# laser_scanner.net
KiCad netlist of a schematic drawn in EAGLE
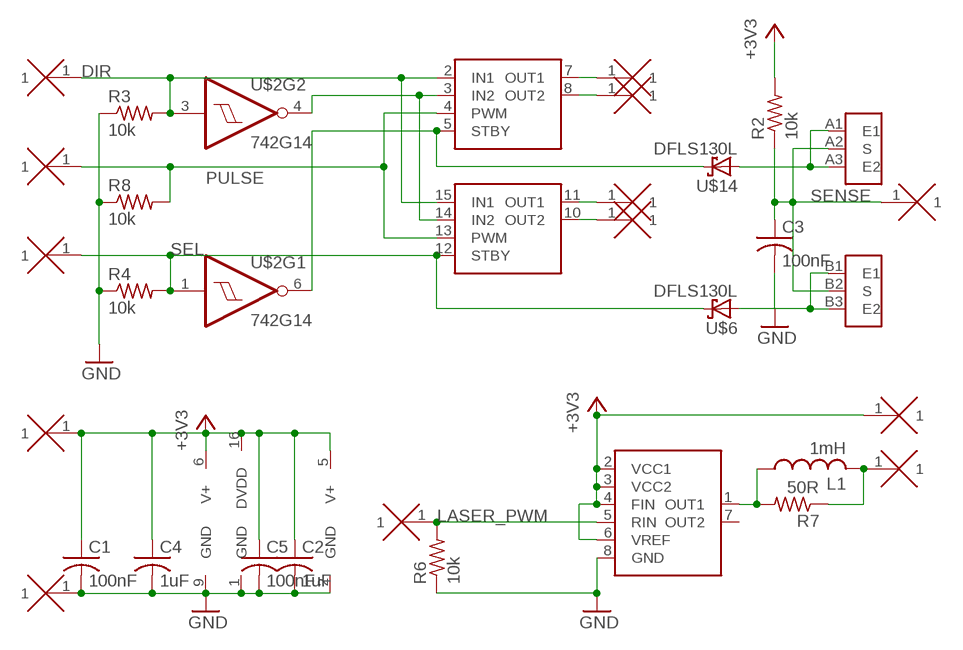
[diagram p0: schematic, sheet 1]

(export (version "E")
  (design (tool "Eeschema 10.0.6"))
  (components
    (comp (ref "C1")
      (value "100nF")
      (footprint "eagle-import:C0603")
      (libsource (lib "eagle-import") (part "C-USC0603"))
    )
    (comp (ref "C2")
      (value "1uF")
      (footprint "eagle-import:C0603")
      (libsource (lib "eagle-import") (part "C-USC0603"))
    )
    (comp (ref "C3")
      (value "100nF")
      (footprint "eagle-import:C0603")
      (libsource (lib "eagle-import") (part "C-USC0603"))
    )
    (comp (ref "C4")
      (value "1uF")
      (footprint "eagle-import:C0603")
      (libsource (lib "eagle-import") (part "C-USC0603"))
    )
    (comp (ref "C5")
      (value "100nF")
      (footprint "eagle-import:C0603")
      (libsource (lib "eagle-import") (part "C-USC0603"))
    )
    (comp (ref "GALVO_DIR")
      (value "PAD-0.6_1.8")
      (footprint "eagle-import:PAD_0.6_1.8")
      (libsource (lib "eagle-import") (part "PAD-0.6_1.8"))
    )
    (comp (ref "GALVO_PULSE")
      (value "PAD-0.6_1.8")
      (footprint "eagle-import:PAD_0.6_1.8")
      (libsource (lib "eagle-import") (part "PAD-0.6_1.8"))
    )
    (comp (ref "GALVO_SEL")
      (value "PAD-0.6_1.8")
      (footprint "eagle-import:PAD_0.6_1.8")
      (libsource (lib "eagle-import") (part "PAD-0.6_1.8"))
    )
    (comp (ref "GALVO_SENSE")
      (value "PAD-0.6_1.8")
      (footprint "eagle-import:PAD_0.6_1.8")
      (libsource (lib "eagle-import") (part "PAD-0.6_1.8"))
    )
    (comp (ref "GND")
      (value "PAD-0.6_1.8")
      (footprint "eagle-import:PAD_0.6_1.8")
      (libsource (lib "eagle-import") (part "PAD-0.6_1.8"))
    )
    (comp (ref "L+")
      (value "PAD-0.6_1.8")
      (footprint "eagle-import:PAD_0.6_1.8")
      (libsource (lib "eagle-import") (part "PAD-0.6_1.8"))
    )
    (comp (ref "L-")
      (value "PAD-0.6_1.8")
      (footprint "eagle-import:PAD_0.6_1.8")
      (libsource (lib "eagle-import") (part "PAD-0.6_1.8"))
    )
    (comp (ref "L1")
      (value "1mH")
      (footprint "eagle-import:L7070")
      (libsource (lib "eagle-import") (part "L-US"))
    )
    (comp (ref "LASER_PWM")
      (value "PAD-0.6_1.8")
      (footprint "eagle-import:PAD_0.6_1.8")
      (libsource (lib "eagle-import") (part "PAD-0.6_1.8"))
    )
    (comp (ref "MA1")
      (value "PAD-0.6_1.8")
      (footprint "eagle-import:PAD_0.6_1.8")
      (libsource (lib "eagle-import") (part "PAD-0.6_1.8"))
    )
    (comp (ref "MA2")
      (value "PAD-0.6_1.8")
      (footprint "eagle-import:PAD_0.6_1.8")
      (libsource (lib "eagle-import") (part "PAD-0.6_1.8"))
    )
    (comp (ref "MB1")
      (value "PAD-0.6_1.8")
      (footprint "eagle-import:PAD_0.6_1.8")
      (libsource (lib "eagle-import") (part "PAD-0.6_1.8"))
    )
    (comp (ref "MB2")
      (value "PAD-0.6_1.8")
      (footprint "eagle-import:PAD_0.6_1.8")
      (libsource (lib "eagle-import") (part "PAD-0.6_1.8"))
    )
    (comp (ref "R2")
      (value "10k")
      (footprint "eagle-import:R0603")
      (libsource (lib "eagle-import") (part "R-US_R0603"))
    )
    (comp (ref "R3")
      (value "10k")
      (footprint "eagle-import:R0603")
      (libsource (lib "eagle-import") (part "R-US_R0603"))
    )
    (comp (ref "R4")
      (value "10k")
      (footprint "eagle-import:R0603")
      (libsource (lib "eagle-import") (part "R-US_R0603"))
    )
    (comp (ref "R6")
      (value "10k")
      (footprint "eagle-import:R0603")
      (libsource (lib "eagle-import") (part "R-US_R0603"))
    )
    (comp (ref "R7")
      (value "50R")
      (footprint "eagle-import:R0603")
      (libsource (lib "eagle-import") (part "R-US_R0603"))
    )
    (comp (ref "R8")
      (value "10k")
      (footprint "eagle-import:R0603")
      (libsource (lib "eagle-import") (part "R-US_R0603"))
    )
    (comp (ref "U$1")
      (value "TB6552")
      (footprint "eagle-import:TSSOP16")
      (libsource (lib "eagle-import") (part "TB6552"))
    )
    (comp (ref "U$2")
      (value "742G14")
      (footprint "eagle-import:SOT23-6")
      (libsource (lib "eagle-import") (part "742G14"))
    )
    (comp (ref "U$3")
      (value "BD6211")
      (footprint "eagle-import:SOP-08")
      (libsource (lib "eagle-import") (part "BD6211"))
    )
    (comp (ref "U$6")
      (value "DFLS130L")
      (footprint "eagle-import:POWERDI323")
      (libsource (lib "eagle-import") (part "DFLS130L"))
    )
    (comp (ref "U$7")
      (value "LASER_SLIDER")
      (footprint "eagle-import:LASER_SCANNER")
      (libsource (lib "eagle-import") (part "LASER_SLIDER"))
    )
    (comp (ref "U$14")
      (value "DFLS130L")
      (footprint "eagle-import:POWERDI323")
      (libsource (lib "eagle-import") (part "DFLS130L"))
    )
    (comp (ref "VCC")
      (value "PAD-0.6_1.8")
      (footprint "eagle-import:PAD_0.6_1.8")
      (libsource (lib "eagle-import") (part "PAD-0.6_1.8"))
    )
  )
  (nets
    (net (code "1") (name "+3V3") (class "Default")
      (node (ref "C1") (pin "1") (pinfunction "1_1") (pintype "passive"))
      (node (ref "C2") (pin "1") (pinfunction "1_1") (pintype "passive"))
      (node (ref "C4") (pin "1") (pinfunction "1_1") (pintype "passive"))
      (node (ref "C5") (pin "1") (pinfunction "1_1") (pintype "passive"))
      (node (ref "L+") (pin "1") (pinfunction "1_1") (pintype "bidirectional"))
      (node (ref "R2") (pin "2") (pinfunction "2_2") (pintype "passive"))
      (node (ref "U$1") (pin "16") (pinfunction "DVDD_16") (pintype "bidirectional"))
      (node (ref "U$1") (pin "6") (pinfunction "V+_6") (pintype "power_in"))
      (node (ref "U$2") (pin "5") (pinfunction "V+_5") (pintype "power_in"))
      (node (ref "U$3") (pin "2") (pinfunction "VCC1_2") (pintype "bidirectional"))
      (node (ref "U$3") (pin "3") (pinfunction "VCC2_3") (pintype "bidirectional"))
      (node (ref "U$3") (pin "4") (pinfunction "FIN_4") (pintype "bidirectional"))
      (node (ref "U$3") (pin "6") (pinfunction "VREF_6") (pintype "bidirectional"))
      (node (ref "VCC") (pin "1") (pinfunction "1_1") (pintype "bidirectional"))
    )
    (net (code "2") (name "/DIR") (class "Default")
      (node (ref "GALVO_DIR") (pin "1") (pinfunction "1_1") (pintype "bidirectional"))
      (node (ref "R3") (pin "2") (pinfunction "2_2") (pintype "passive"))
      (node (ref "U$1") (pin "15") (pinfunction "IN1_15") (pintype "bidirectional"))
      (node (ref "U$1") (pin "2") (pinfunction "IN1_2") (pintype "bidirectional"))
      (node (ref "U$2") (pin "3") (pinfunction "I_3") (pintype "input"))
    )
    (net (code "3") (name "/LASER_PWM") (class "Default")
      (node (ref "LASER_PWM") (pin "1") (pinfunction "1_1") (pintype "bidirectional"))
      (node (ref "R6") (pin "2") (pinfunction "2_2") (pintype "passive"))
      (node (ref "U$3") (pin "5") (pinfunction "RIN_5") (pintype "bidirectional"))
    )
    (net (code "4") (name "/PULSE") (class "Default")
      (node (ref "GALVO_PULSE") (pin "1") (pinfunction "1_1") (pintype "bidirectional"))
      (node (ref "R8") (pin "2") (pinfunction "2_2") (pintype "passive"))
      (node (ref "U$1") (pin "13") (pinfunction "PWM_13") (pintype "bidirectional"))
      (node (ref "U$1") (pin "4") (pinfunction "PWM_4") (pintype "bidirectional"))
    )
    (net (code "5") (name "/SEL") (class "Default")
      (node (ref "GALVO_SEL") (pin "1") (pinfunction "1_1") (pintype "bidirectional"))
      (node (ref "R4") (pin "2") (pinfunction "2_2") (pintype "passive"))
      (node (ref "U$1") (pin "12") (pinfunction "STBY_12") (pintype "bidirectional"))
      (node (ref "U$2") (pin "1") (pinfunction "I_1") (pintype "input"))
      (node (ref "U$6") (pin "C") (pinfunction "C_C") (pintype "passive"))
    )
    (net (code "6") (name "/SENSE") (class "Default")
      (node (ref "C3") (pin "1") (pinfunction "1_1") (pintype "passive"))
      (node (ref "GALVO_SENSE") (pin "1") (pinfunction "1_1") (pintype "bidirectional"))
      (node (ref "R2") (pin "1") (pinfunction "1_1") (pintype "passive"))
      (node (ref "U$7") (pin "A2") (pinfunction "S_A2") (pintype "bidirectional"))
      (node (ref "U$7") (pin "B2") (pinfunction "S_B2") (pintype "bidirectional"))
    )
    (net (code "7") (name "GND") (class "Default")
      (node (ref "C1") (pin "2") (pinfunction "2_2") (pintype "passive"))
      (node (ref "C2") (pin "2") (pinfunction "2_2") (pintype "passive"))
      (node (ref "C3") (pin "2") (pinfunction "2_2") (pintype "passive"))
      (node (ref "C4") (pin "2") (pinfunction "2_2") (pintype "passive"))
      (node (ref "C5") (pin "2") (pinfunction "2_2") (pintype "passive"))
      (node (ref "GND") (pin "1") (pinfunction "1_1") (pintype "bidirectional"))
      (node (ref "R3") (pin "1") (pinfunction "1_1") (pintype "passive"))
      (node (ref "R4") (pin "1") (pinfunction "1_1") (pintype "passive"))
      (node (ref "R6") (pin "1") (pinfunction "1_1") (pintype "passive"))
      (node (ref "R8") (pin "1") (pinfunction "1_1") (pintype "passive"))
      (node (ref "U$1") (pin "1") (pinfunction "GND_1") (pintype "bidirectional"))
      (node (ref "U$1") (pin "9") (pinfunction "GND_9") (pintype "power_in"))
      (node (ref "U$2") (pin "2") (pinfunction "GND_2") (pintype "power_in"))
      (node (ref "U$3") (pin "8") (pinfunction "GND_8") (pintype "bidirectional"))
    )
    (net (code "8") (name "Net-(L--Pad1)") (class "Default")
      (node (ref "L-") (pin "1") (pinfunction "1_1") (pintype "bidirectional"))
      (node (ref "L1") (pin "2") (pinfunction "2_2") (pintype "passive"))
      (node (ref "R7") (pin "1") (pinfunction "1_1") (pintype "passive"))
    )
    (net (code "9") (name "Net-(U$1A-IN2)") (class "Default")
      (node (ref "U$1") (pin "14") (pinfunction "IN2_14") (pintype "bidirectional"))
      (node (ref "U$1") (pin "3") (pinfunction "IN2_3") (pintype "bidirectional"))
      (node (ref "U$2") (pin "4") (pinfunction "O_4") (pintype "output"))
    )
    (net (code "10") (name "Net-(U$1A-OUT1)") (class "Default")
      (node (ref "MB1") (pin "1") (pinfunction "1_1") (pintype "bidirectional"))
      (node (ref "U$1") (pin "7") (pinfunction "OUT1_7") (pintype "bidirectional"))
    )
    (net (code "11") (name "Net-(U$1A-OUT2)") (class "Default")
      (node (ref "MB2") (pin "1") (pinfunction "1_1") (pintype "bidirectional"))
      (node (ref "U$1") (pin "8") (pinfunction "OUT2_8") (pintype "bidirectional"))
    )
    (net (code "12") (name "Net-(U$1A-STBY)") (class "Default")
      (node (ref "U$1") (pin "5") (pinfunction "STBY_5") (pintype "bidirectional"))
      (node (ref "U$14") (pin "C") (pinfunction "C_C") (pintype "passive"))
      (node (ref "U$2") (pin "6") (pinfunction "O_6") (pintype "output"))
    )
    (net (code "13") (name "Net-(U$1B-OUT1)") (class "Default")
      (node (ref "MA1") (pin "1") (pinfunction "1_1") (pintype "bidirectional"))
      (node (ref "U$1") (pin "11") (pinfunction "OUT1_11") (pintype "bidirectional"))
    )
    (net (code "14") (name "Net-(U$1B-OUT2)") (class "Default")
      (node (ref "MA2") (pin "1") (pinfunction "1_1") (pintype "bidirectional"))
      (node (ref "U$1") (pin "10") (pinfunction "OUT2_10") (pintype "bidirectional"))
    )
    (net (code "15") (name "Net-(U$3-OUT1)") (class "Default")
      (node (ref "L1") (pin "1") (pinfunction "1_1") (pintype "passive"))
      (node (ref "R7") (pin "2") (pinfunction "2_2") (pintype "passive"))
      (node (ref "U$3") (pin "1") (pinfunction "OUT1_1") (pintype "bidirectional"))
    )
    (net (code "16") (name "Net-(U$7A-E1)") (class "Default")
      (node (ref "U$14") (pin "A") (pinfunction "A_A") (pintype "passive"))
      (node (ref "U$7") (pin "A1") (pinfunction "E1_A1") (pintype "bidirectional"))
      (node (ref "U$7") (pin "A3") (pinfunction "E2_A3") (pintype "bidirectional"))
    )
    (net (code "17") (name "Net-(U$7B-E1)") (class "Default")
      (node (ref "U$6") (pin "A") (pinfunction "A_A") (pintype "passive"))
      (node (ref "U$7") (pin "B1") (pinfunction "E1_B1") (pintype "bidirectional"))
      (node (ref "U$7") (pin "B3") (pinfunction "E2_B3") (pintype "bidirectional"))
    )
    (net (code "18") (name "unconnected-(U$3-OUT2-Pad7)") (class "Default")
      (node (ref "U$3") (pin "7") (pinfunction "OUT2_7") (pintype "bidirectional"))
    )
  )
)
